# Input.net
KiCad netlist of a schematic drawn in Altium Designer
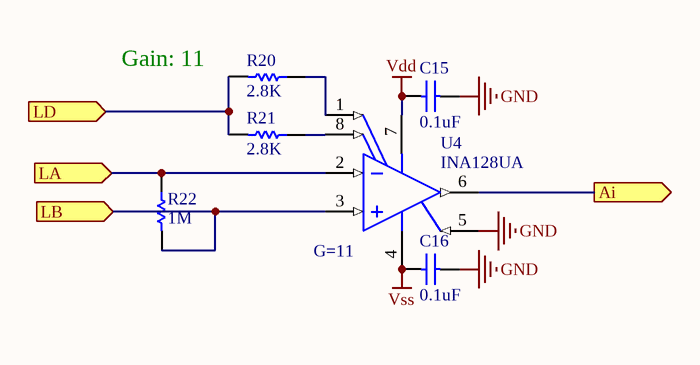
[diagram p0: Input.SchDoc]

(export (version "E")
  (design (tool "Eeschema 10.0.6"))
  (components
    (comp (ref "C15")
      (value "0.1uF")
      (footprint "C0805")
      (description "Capacitor")
      (fields (field (name "Comment") "Cap") (field (name "PUBLISHER") "Altium Limited"))
      (libsource (lib "Miscellaneous Devices") (part "Cap"))
    )
    (comp (ref "C16")
      (value "0.1uF")
      (footprint "C0805")
      (description "Capacitor")
      (fields (field (name "Comment") "Cap") (field (name "PUBLISHER") "Altium Limited"))
      (libsource (lib "Miscellaneous Devices") (part "Cap"))
    )
    (comp (ref "R20")
      (value "2.8K")
      (footprint "C1206")
      (description "Resistor")
      (fields (field (name "Comment") "Res1") (field (name "PUBLISHER") "Altium Limited"))
      (libsource (lib "Miscellaneous Devices") (part "Res1"))
    )
    (comp (ref "R21")
      (value "2.8K")
      (footprint "C1206")
      (description "Resistor")
      (fields (field (name "Comment") "Res1") (field (name "PUBLISHER") "Altium Limited"))
      (libsource (lib "Miscellaneous Devices") (part "Res1"))
    )
    (comp (ref "R22")
      (value "1M")
      (footprint "C1206")
      (description "Resistor")
      (fields (field (name "Comment") "Res1") (field (name "PUBLISHER") "Altium Limited"))
      (libsource (lib "Miscellaneous Devices") (part "Res1"))
    )
    (comp (ref "U4")
      (value "INA128UA")
      (footprint "TI-D8_N")
      (fields (field (name "MANUFACTURER") "Texas Instruments"))
      (libsource (lib "TI Amplifiers and Linear Instrumentation Amplifier") (part "INA128UA"))
    )
  )
  (nets
    (net (code "1") (name "/Ai") (class "Default")
      (node (ref "U4") (pin "6") (pinfunction "VO_6") (pintype "output"))
    )
    (net (code "2") (name "/LA") (class "Default")
      (node (ref "R22") (pin "1") (pinfunction "1_1") (pintype "passive"))
      (node (ref "U4") (pin "2") (pinfunction "VIN-_2") (pintype "input"))
    )
    (net (code "3") (name "/LB") (class "Default")
      (node (ref "R22") (pin "2") (pinfunction "2_2") (pintype "passive"))
      (node (ref "U4") (pin "3") (pinfunction "VIN+_3") (pintype "input"))
    )
    (net (code "4") (name "/LD") (class "Default")
      (node (ref "R20") (pin "2") (pinfunction "2_2") (pintype "passive"))
      (node (ref "R21") (pin "2") (pinfunction "2_2") (pintype "passive"))
    )
    (net (code "5") (name "GND") (class "Default")
      (node (ref "C15") (pin "1") (pinfunction "1_1") (pintype "passive"))
      (node (ref "C16") (pin "1") (pinfunction "1_1") (pintype "passive"))
      (node (ref "U4") (pin "5") (pinfunction "REF_5") (pintype "input"))
    )
    (net (code "6") (name "Net-(R20-Pad1)") (class "Default")
      (node (ref "R20") (pin "1") (pinfunction "1_1") (pintype "passive"))
      (node (ref "U4") (pin "1") (pinfunction "RG_1") (pintype "input"))
    )
    (net (code "7") (name "Net-(R21-Pad1)") (class "Default")
      (node (ref "R21") (pin "1") (pinfunction "1_1") (pintype "passive"))
      (node (ref "U4") (pin "8") (pinfunction "RG_8") (pintype "input"))
    )
    (net (code "8") (name "Vdd") (class "Default")
      (node (ref "C15") (pin "2") (pinfunction "2_2") (pintype "passive"))
      (node (ref "U4") (pin "7") (pinfunction "V+_7") (pintype "power_in"))
    )
    (net (code "9") (name "Vss") (class "Default")
      (node (ref "C16") (pin "2") (pinfunction "2_2") (pintype "passive"))
      (node (ref "U4") (pin "4") (pinfunction "V-_4") (pintype "power_in"))
    )
  )
)
